# micromouse_v35.net
KiCad netlist of a schematic drawn in EAGLE
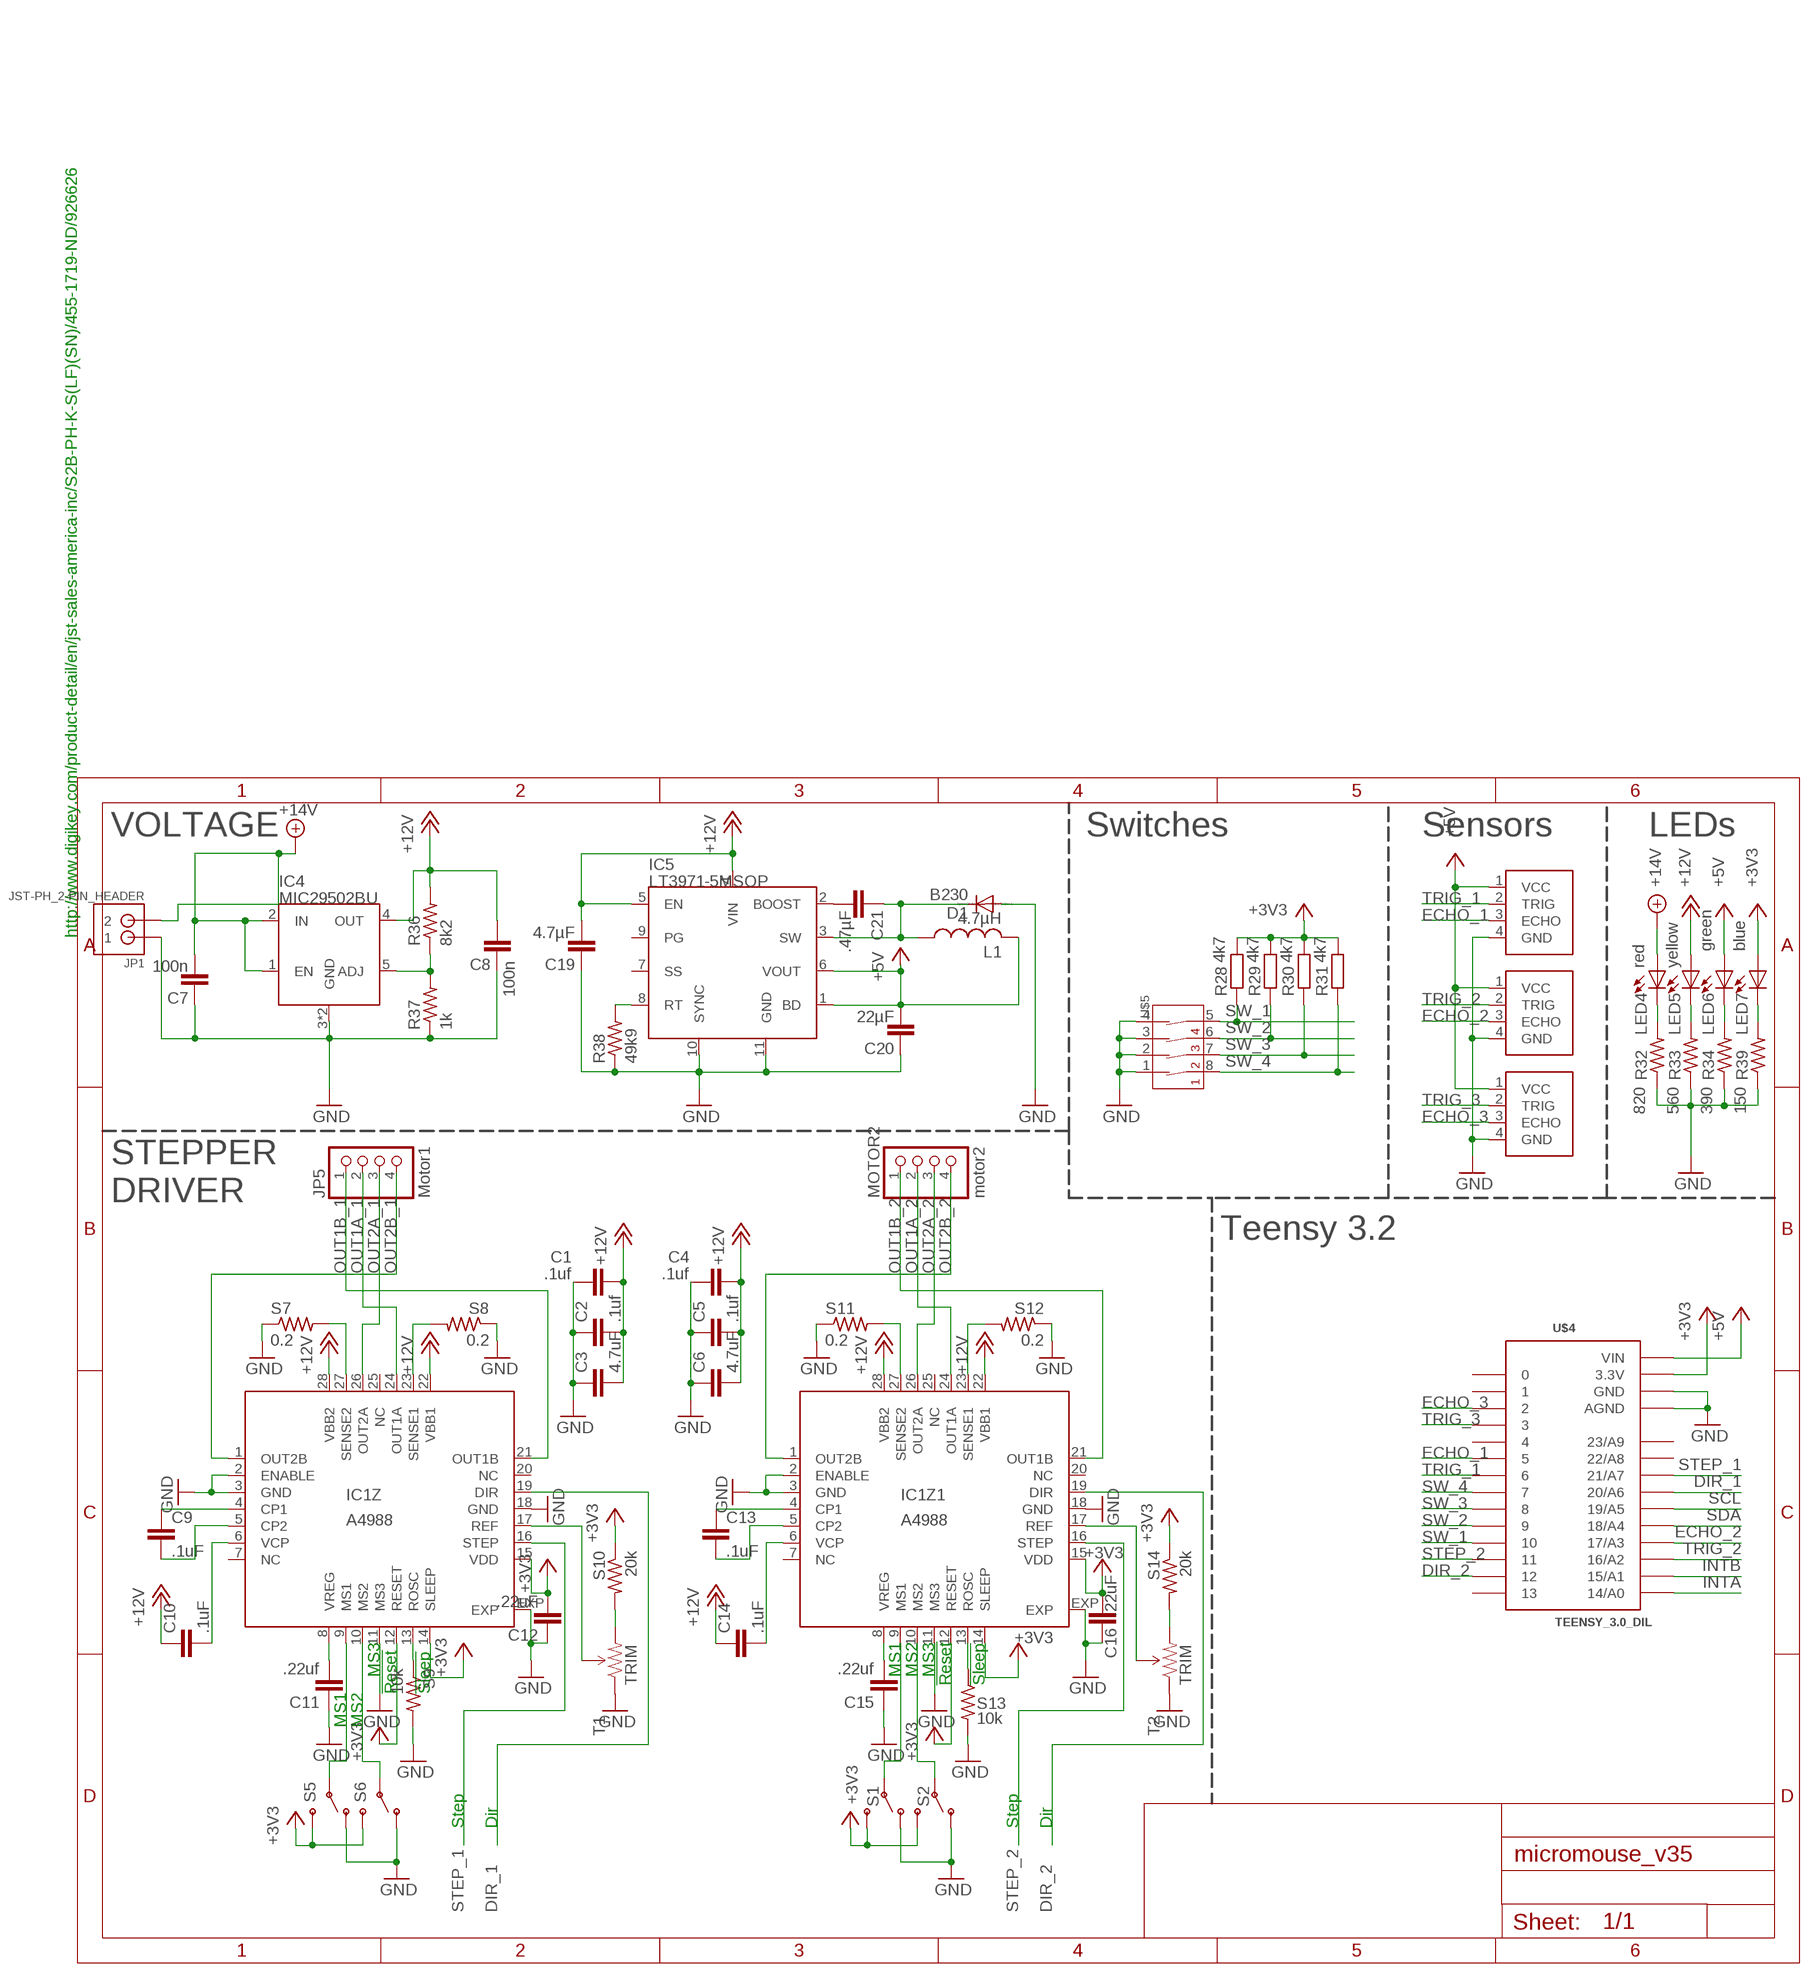
[diagram p0: schematic, sheet 1]

(export (version "E")
  (design (tool "Eeschema 10.0.6"))
  (components
    (comp (ref "C1")
      (value ".1uf")
      (footprint "eagle-import:C0603")
      (libsource (lib "eagle-import") (part "C-EUC0603"))
    )
    (comp (ref "C2")
      (value ".1uf")
      (footprint "eagle-import:C0603")
      (libsource (lib "eagle-import") (part "C-EUC0603"))
    )
    (comp (ref "C3")
      (value "4.7uF")
      (footprint "eagle-import:1206")
      (libsource (lib "eagle-import") (part "CAP1206"))
    )
    (comp (ref "C4")
      (value ".1uf")
      (footprint "eagle-import:C0603")
      (libsource (lib "eagle-import") (part "C-EUC0603"))
    )
    (comp (ref "C5")
      (value ".1uf")
      (footprint "eagle-import:C0603")
      (libsource (lib "eagle-import") (part "C-EUC0603"))
    )
    (comp (ref "C6")
      (value "4.7uF")
      (footprint "eagle-import:1206")
      (libsource (lib "eagle-import") (part "CAP1206"))
    )
    (comp (ref "C7")
      (value "100n")
      (footprint "eagle-import:C0603")
      (libsource (lib "eagle-import") (part "C-EUC0603"))
    )
    (comp (ref "C8")
      (value "100n")
      (footprint "eagle-import:C0603")
      (libsource (lib "eagle-import") (part "C-EUC0603"))
    )
    (comp (ref "C9")
      (value ".1uF")
      (footprint "eagle-import:C0603")
      (libsource (lib "eagle-import") (part "C-EUC0603"))
    )
    (comp (ref "C10")
      (value ".1uF")
      (footprint "eagle-import:C0603")
      (libsource (lib "eagle-import") (part "C-EUC0603"))
    )
    (comp (ref "C11")
      (value ".22uf")
      (footprint "eagle-import:C0603")
      (libsource (lib "eagle-import") (part "C-EUC0603"))
    )
    (comp (ref "C12")
      (value ".22uF")
      (footprint "eagle-import:C0603")
      (libsource (lib "eagle-import") (part "C-EUC0603"))
    )
    (comp (ref "C13")
      (value ".1uF")
      (footprint "eagle-import:C0603")
      (libsource (lib "eagle-import") (part "C-EUC0603"))
    )
    (comp (ref "C14")
      (value ".1uF")
      (footprint "eagle-import:C0603")
      (libsource (lib "eagle-import") (part "C-EUC0603"))
    )
    (comp (ref "C15")
      (value ".22uf")
      (footprint "eagle-import:C0603")
      (libsource (lib "eagle-import") (part "C-EUC0603"))
    )
    (comp (ref "C16")
      (value ".22uF")
      (footprint "eagle-import:C0603")
      (libsource (lib "eagle-import") (part "C-EUC0603"))
    )
    (comp (ref "C19")
      (value "4.7µF")
      (footprint "eagle-import:C0603")
      (libsource (lib "eagle-import") (part "C-EUC0603"))
    )
    (comp (ref "C20")
      (value "22µF")
      (footprint "eagle-import:C0805")
      (libsource (lib "eagle-import") (part "C-EUC0805"))
    )
    (comp (ref "C21")
      (value ".47µF")
      (footprint "eagle-import:C0603")
      (libsource (lib "eagle-import") (part "C-EUC0603"))
    )
    (comp (ref "D1")
      (value "B230")
      (footprint "eagle-import:DO-214AC")
      (libsource (lib "eagle-import") (part "DIODE-DO-214AC"))
    )
    (comp (ref "IC1Z")
      (value "A4988")
      (footprint "eagle-import:QFN28ET")
      (fields (field (name "MPN") "A4983SETTR-T"))
      (libsource (lib "eagle-import") (part "A4983"))
    )
    (comp (ref "IC1Z1")
      (value "A4988")
      (footprint "eagle-import:QFN28ET")
      (fields (field (name "MPN") "A4983SETTR-T"))
      (libsource (lib "eagle-import") (part "A4983"))
    )
    (comp (ref "IC4")
      (value "MIC29502BU")
      (footprint "eagle-import:TO-263-5")
      (libsource (lib "eagle-import") (part "MIC29502BU"))
    )
    (comp (ref "IC5")
      (value "LT3971-5MSOP")
      (footprint "eagle-import:MSOP-10")
      (libsource (lib "eagle-import") (part "LT3971-5MSOP"))
    )
    (comp (ref "JP1")
      (value "JST-PH_2-PIN_HEADER")
      (footprint "eagle-import:JST_B2B-PH_HEADER")
      (libsource (lib "eagle-import") (part "JST-PH_2-PIN_HEADER"))
    )
    (comp (ref "JP5")
      (value "Motor1")
      (footprint "eagle-import:1X04")
      (libsource (lib "eagle-import") (part "PINHD-1X4"))
    )
    (comp (ref "L1")
      (value "4.7µH")
      (footprint "eagle-import:L1812")
      (libsource (lib "eagle-import") (part "L-USL1812"))
    )
    (comp (ref "LED4")
      (value "red")
      (footprint "eagle-import:SML0603")
      (libsource (lib "eagle-import") (part "LEDSML0603"))
    )
    (comp (ref "LED5")
      (value "yellow")
      (footprint "eagle-import:SML0603")
      (libsource (lib "eagle-import") (part "LEDSML0603"))
    )
    (comp (ref "LED6")
      (value "green")
      (footprint "eagle-import:SML0603")
      (libsource (lib "eagle-import") (part "LEDSML0603"))
    )
    (comp (ref "LED7")
      (value "blue")
      (footprint "eagle-import:SML0603")
      (libsource (lib "eagle-import") (part "LEDSML0603"))
    )
    (comp (ref "MOTOR2")
      (value "motor2")
      (footprint "eagle-import:1X04")
      (libsource (lib "eagle-import") (part "PINHD-1X4"))
    )
    (comp (ref "R28")
      (value "4k7")
      (footprint "eagle-import:R0603")
      (libsource (lib "eagle-import") (part "R-EU_R0603"))
    )
    (comp (ref "R29")
      (value "4k7")
      (footprint "eagle-import:R0603")
      (libsource (lib "eagle-import") (part "R-EU_R0603"))
    )
    (comp (ref "R30")
      (value "4k7")
      (footprint "eagle-import:R0603")
      (libsource (lib "eagle-import") (part "R-EU_R0603"))
    )
    (comp (ref "R31")
      (value "4k7")
      (footprint "eagle-import:R0603")
      (libsource (lib "eagle-import") (part "R-EU_R0603"))
    )
    (comp (ref "R32")
      (value "820")
      (footprint "eagle-import:R0603")
      (libsource (lib "eagle-import") (part "R-US_R0603"))
    )
    (comp (ref "R33")
      (value "560")
      (footprint "eagle-import:R0603")
      (libsource (lib "eagle-import") (part "R-US_R0603"))
    )
    (comp (ref "R34")
      (value "390")
      (footprint "eagle-import:R0603")
      (libsource (lib "eagle-import") (part "R-US_R0603"))
    )
    (comp (ref "R36")
      (value "8k2")
      (footprint "eagle-import:R0603")
      (libsource (lib "eagle-import") (part "R-US_R0603"))
    )
    (comp (ref "R37")
      (value "1k")
      (footprint "eagle-import:R0603")
      (libsource (lib "eagle-import") (part "R-US_R0603"))
    )
    (comp (ref "R38")
      (value "49k9")
      (footprint "eagle-import:R0603")
      (libsource (lib "eagle-import") (part "R-US_R0603"))
    )
    (comp (ref "R39")
      (value "150")
      (footprint "eagle-import:R0603")
      (libsource (lib "eagle-import") (part "R-US_R0603"))
    )
    (comp (ref "S1")
      (value "SWITCH-SPDT-SMD-A")
      (footprint "eagle-import:SWITCH-SPST-SMD-A")
      (libsource (lib "eagle-import") (part "SWITCH-SPDT-SMD-A"))
    )
    (comp (ref "S2")
      (value "SWITCH-SPDT-SMD-A")
      (footprint "eagle-import:SWITCH-SPST-SMD-A")
      (libsource (lib "eagle-import") (part "SWITCH-SPDT-SMD-A"))
    )
    (comp (ref "S5")
      (value "SWITCH-SPDT-SMD-A")
      (footprint "eagle-import:SWITCH-SPST-SMD-A")
      (libsource (lib "eagle-import") (part "SWITCH-SPDT-SMD-A"))
    )
    (comp (ref "S6")
      (value "SWITCH-SPDT-SMD-A")
      (footprint "eagle-import:SWITCH-SPST-SMD-A")
      (libsource (lib "eagle-import") (part "SWITCH-SPDT-SMD-A"))
    )
    (comp (ref "S7")
      (value "0.2")
      (footprint "eagle-import:R0603")
      (libsource (lib "eagle-import") (part "R-US_R0603"))
    )
    (comp (ref "S8")
      (value "0.2")
      (footprint "eagle-import:R0603")
      (libsource (lib "eagle-import") (part "R-US_R0603"))
    )
    (comp (ref "S9")
      (value "10k")
      (footprint "eagle-import:R0603")
      (libsource (lib "eagle-import") (part "R-US_R0603"))
    )
    (comp (ref "S10")
      (value "20k")
      (footprint "eagle-import:R0603")
      (libsource (lib "eagle-import") (part "R-US_R0603"))
    )
    (comp (ref "S11")
      (value "0.2")
      (footprint "eagle-import:R0603")
      (libsource (lib "eagle-import") (part "R-US_R0603"))
    )
    (comp (ref "S12")
      (value "0.2")
      (footprint "eagle-import:R0603")
      (libsource (lib "eagle-import") (part "R-US_R0603"))
    )
    (comp (ref "S13")
      (value "10k")
      (footprint "eagle-import:R0603")
      (libsource (lib "eagle-import") (part "R-US_R0603"))
    )
    (comp (ref "S14")
      (value "20k")
      (footprint "eagle-import:R0603")
      (libsource (lib "eagle-import") (part "R-US_R0603"))
    )
    (comp (ref "SENSOR1")
      (value "HC-SR04SMD")
      (footprint "eagle-import:HC-SR04_SMD")
      (libsource (lib "eagle-import") (part "HC-SR04SMD"))
    )
    (comp (ref "SENSOR2")
      (value "HC-SR04SMD")
      (footprint "eagle-import:HC-SR04_SMD")
      (libsource (lib "eagle-import") (part "HC-SR04SMD"))
    )
    (comp (ref "SENSOR3")
      (value "HC-SR04SMD")
      (footprint "eagle-import:HC-SR04_SMD")
      (libsource (lib "eagle-import") (part "HC-SR04SMD"))
    )
    (comp (ref "T1")
      (value "TRIM")
      (footprint "eagle-import:TRIMPOT-3MM")
      (libsource (lib "eagle-import") (part "TRIMPOTSMD"))
    )
    (comp (ref "T2")
      (value "TRIM")
      (footprint "eagle-import:TRIMPOT-3MM")
      (libsource (lib "eagle-import") (part "TRIMPOTSMD"))
    )
    (comp (ref "U$4")
      (value "TEENSY_3.0_DIL")
      (footprint "eagle-import:TEENSY3-DIL")
      (libsource (lib "eagle-import") (part "TEENSY_3.0_DIL"))
    )
    (comp (ref "U$5")
      (value "4-POS-DIP")
      (footprint "eagle-import:4-POS-DIP-SMD")
      (libsource (lib "eagle-import") (part "4-POS-DIP"))
    )
  )
  (nets
    (net (code "1") (name "+3V3") (class "Default")
      (node (ref "C12") (pin "2") (pinfunction "2_2") (pintype "passive"))
      (node (ref "C16") (pin "2") (pinfunction "2_2") (pintype "passive"))
      (node (ref "IC1Z") (pin "12") (pinfunction "RESET_12") (pintype "input"))
      (node (ref "IC1Z") (pin "14") (pinfunction "SLEEP_14") (pintype "input"))
      (node (ref "IC1Z") (pin "15") (pinfunction "VDD_15") (pintype "power_in"))
      (node (ref "IC1Z1") (pin "12") (pinfunction "RESET_12") (pintype "input"))
      (node (ref "IC1Z1") (pin "14") (pinfunction "SLEEP_14") (pintype "input"))
      (node (ref "IC1Z1") (pin "15") (pinfunction "VDD_15") (pintype "power_in"))
      (node (ref "LED7") (pin "A") (pinfunction "A_A") (pintype "passive"))
      (node (ref "R28") (pin "2") (pinfunction "2_2") (pintype "passive"))
      (node (ref "R29") (pin "2") (pinfunction "2_2") (pintype "passive"))
      (node (ref "R30") (pin "2") (pinfunction "2_2") (pintype "passive"))
      (node (ref "R31") (pin "2") (pinfunction "2_2") (pintype "passive"))
      (node (ref "S1") (pin "3") (pinfunction "S_3") (pintype "passive"))
      (node (ref "S10") (pin "1") (pinfunction "1_1") (pintype "passive"))
      (node (ref "S14") (pin "1") (pinfunction "1_1") (pintype "passive"))
      (node (ref "S2") (pin "3") (pinfunction "S_3") (pintype "passive"))
      (node (ref "S5") (pin "3") (pinfunction "S_3") (pintype "passive"))
      (node (ref "S6") (pin "3") (pinfunction "S_3") (pintype "passive"))
      (node (ref "U$4") (pin "3.3V") (pinfunction "3.3V_3.3V") (pintype "power_in"))
    )
    (net (code "2") (name "+5V") (class "Default")
      (node (ref "C20") (pin "2") (pinfunction "2_2") (pintype "passive"))
      (node (ref "IC5") (pin "1") (pinfunction "BD_1") (pintype "bidirectional"))
      (node (ref "IC5") (pin "6") (pinfunction "VOUT_6") (pintype "bidirectional"))
      (node (ref "L1") (pin "2") (pinfunction "2_2") (pintype "passive"))
      (node (ref "LED6") (pin "A") (pinfunction "A_A") (pintype "passive"))
      (node (ref "SENSOR1") (pin "1") (pinfunction "VCC_1") (pintype "power_in"))
      (node (ref "SENSOR2") (pin "1") (pinfunction "VCC_1") (pintype "power_in"))
      (node (ref "SENSOR3") (pin "1") (pinfunction "VCC_1") (pintype "power_in"))
      (node (ref "U$4") (pin "VIN") (pinfunction "VIN_VIN") (pintype "power_in"))
    )
    (net (code "3") (name "+12V") (class "Default")
      (node (ref "C1") (pin "2") (pinfunction "2_2") (pintype "passive"))
      (node (ref "C10") (pin "1") (pinfunction "1_1") (pintype "passive"))
      (node (ref "C14") (pin "1") (pinfunction "1_1") (pintype "passive"))
      (node (ref "C19") (pin "2") (pinfunction "2_2") (pintype "passive"))
      (node (ref "C2") (pin "2") (pinfunction "2_2") (pintype "passive"))
      (node (ref "C3") (pin "2") (pinfunction "2_2") (pintype "passive"))
      (node (ref "C4") (pin "2") (pinfunction "2_2") (pintype "passive"))
      (node (ref "C5") (pin "2") (pinfunction "2_2") (pintype "passive"))
      (node (ref "C6") (pin "2") (pinfunction "2_2") (pintype "passive"))
      (node (ref "C8") (pin "2") (pinfunction "2_2") (pintype "passive"))
      (node (ref "IC1Z") (pin "22") (pinfunction "VBB1_22") (pintype "power_in"))
      (node (ref "IC1Z") (pin "28") (pinfunction "VBB2_28") (pintype "power_in"))
      (node (ref "IC1Z1") (pin "22") (pinfunction "VBB1_22") (pintype "power_in"))
      (node (ref "IC1Z1") (pin "28") (pinfunction "VBB2_28") (pintype "power_in"))
      (node (ref "IC4") (pin "4") (pinfunction "OUT_4") (pintype "power_in"))
      (node (ref "IC5") (pin "4") (pinfunction "VIN_4") (pintype "bidirectional"))
      (node (ref "IC5") (pin "5") (pinfunction "EN_5") (pintype "bidirectional"))
      (node (ref "LED5") (pin "A") (pinfunction "A_A") (pintype "passive"))
      (node (ref "R36") (pin "2") (pinfunction "2_2") (pintype "passive"))
    )
    (net (code "4") (name "+14V") (class "Default")
      (node (ref "C7") (pin "2") (pinfunction "2_2") (pintype "passive"))
      (node (ref "IC4") (pin "1") (pinfunction "EN_1") (pintype "input"))
      (node (ref "IC4") (pin "2") (pinfunction "IN_2") (pintype "input"))
      (node (ref "JP1") (pin "P2") (pinfunction "2_P2") (pintype "bidirectional"))
      (node (ref "LED4") (pin "A") (pinfunction "A_A") (pintype "passive"))
    )
    (net (code "5") (name "/DIR_1") (class "Default")
      (node (ref "IC1Z") (pin "19") (pinfunction "DIR_19") (pintype "input"))
      (node (ref "U$4") (pin "20/A6") (pinfunction "20/A6_20/A6") (pintype "bidirectional"))
    )
    (net (code "6") (name "/DIR_2") (class "Default")
      (node (ref "IC1Z1") (pin "19") (pinfunction "DIR_19") (pintype "input"))
      (node (ref "U$4") (pin "12") (pinfunction "12_12") (pintype "bidirectional"))
    )
    (net (code "7") (name "/ECHO_1") (class "Default")
      (node (ref "SENSOR1") (pin "3") (pinfunction "ECHO_3") (pintype "bidirectional"))
      (node (ref "U$4") (pin "5") (pinfunction "5_5") (pintype "bidirectional"))
    )
    (net (code "8") (name "/ECHO_2") (class "Default")
      (node (ref "SENSOR2") (pin "3") (pinfunction "ECHO_3") (pintype "bidirectional"))
      (node (ref "U$4") (pin "17/A3") (pinfunction "17/A3_17/A3") (pintype "bidirectional"))
    )
    (net (code "9") (name "/ECHO_3") (class "Default")
      (node (ref "SENSOR3") (pin "3") (pinfunction "ECHO_3") (pintype "bidirectional"))
      (node (ref "U$4") (pin "2") (pinfunction "2_2") (pintype "bidirectional"))
    )
    (net (code "10") (name "/INTA") (class "Default")
      (node (ref "U$4") (pin "14/A0") (pinfunction "14/A0_14/A0") (pintype "bidirectional"))
    )
    (net (code "11") (name "/INTB") (class "Default")
      (node (ref "U$4") (pin "15/A1") (pinfunction "15/A1_15/A1") (pintype "bidirectional"))
    )
    (net (code "12") (name "/OUT1A_1") (class "Default")
      (node (ref "IC1Z") (pin "24") (pinfunction "OUT1A_24") (pintype "output"))
      (node (ref "JP5") (pin "2") (pinfunction "2_2") (pintype "passive"))
    )
    (net (code "13") (name "/OUT1A_2") (class "Default")
      (node (ref "IC1Z1") (pin "24") (pinfunction "OUT1A_24") (pintype "output"))
      (node (ref "MOTOR2") (pin "2") (pinfunction "2_2") (pintype "passive"))
    )
    (net (code "14") (name "/OUT1B_1") (class "Default")
      (node (ref "IC1Z") (pin "21") (pinfunction "OUT1B_21") (pintype "output"))
      (node (ref "JP5") (pin "1") (pinfunction "1_1") (pintype "passive"))
    )
    (net (code "15") (name "/OUT1B_2") (class "Default")
      (node (ref "IC1Z1") (pin "21") (pinfunction "OUT1B_21") (pintype "output"))
      (node (ref "MOTOR2") (pin "1") (pinfunction "1_1") (pintype "passive"))
    )
    (net (code "16") (name "/OUT2A_1") (class "Default")
      (node (ref "IC1Z") (pin "26") (pinfunction "OUT2A_26") (pintype "output"))
      (node (ref "JP5") (pin "3") (pinfunction "3_3") (pintype "passive"))
    )
    (net (code "17") (name "/OUT2A_2") (class "Default")
      (node (ref "IC1Z1") (pin "26") (pinfunction "OUT2A_26") (pintype "output"))
      (node (ref "MOTOR2") (pin "3") (pinfunction "3_3") (pintype "passive"))
    )
    (net (code "18") (name "/OUT2B_1") (class "Default")
      (node (ref "IC1Z") (pin "1") (pinfunction "OUT2B_1") (pintype "output"))
      (node (ref "JP5") (pin "4") (pinfunction "4_4") (pintype "passive"))
    )
    (net (code "19") (name "/OUT2B_2") (class "Default")
      (node (ref "IC1Z1") (pin "1") (pinfunction "OUT2B_1") (pintype "output"))
      (node (ref "MOTOR2") (pin "4") (pinfunction "4_4") (pintype "passive"))
    )
    (net (code "20") (name "/SCL") (class "Default")
      (node (ref "U$4") (pin "19/A5") (pinfunction "19/A5_19/A5") (pintype "bidirectional"))
    )
    (net (code "21") (name "/SDA") (class "Default")
      (node (ref "U$4") (pin "18/A4") (pinfunction "18/A4_18/A4") (pintype "bidirectional"))
    )
    (net (code "22") (name "/STEP_1") (class "Default")
      (node (ref "IC1Z") (pin "16") (pinfunction "STEP_16") (pintype "input"))
      (node (ref "U$4") (pin "21/A7") (pinfunction "21/A7_21/A7") (pintype "bidirectional"))
    )
    (net (code "23") (name "/STEP_2") (class "Default")
      (node (ref "IC1Z1") (pin "16") (pinfunction "STEP_16") (pintype "input"))
      (node (ref "U$4") (pin "11") (pinfunction "11_11") (pintype "bidirectional"))
    )
    (net (code "24") (name "/SW_1") (class "Default")
      (node (ref "R28") (pin "1") (pinfunction "1_1") (pintype "passive"))
      (node (ref "U$4") (pin "10") (pinfunction "10_10") (pintype "bidirectional"))
      (node (ref "U$5") (pin "5") (pinfunction "4B_5") (pintype "bidirectional"))
    )
    (net (code "25") (name "/SW_2") (class "Default")
      (node (ref "R29") (pin "1") (pinfunction "1_1") (pintype "passive"))
      (node (ref "U$4") (pin "9") (pinfunction "9_9") (pintype "bidirectional"))
      (node (ref "U$5") (pin "6") (pinfunction "3B_6") (pintype "bidirectional"))
    )
    (net (code "26") (name "/SW_3") (class "Default")
      (node (ref "R30") (pin "1") (pinfunction "1_1") (pintype "passive"))
      (node (ref "U$4") (pin "8") (pinfunction "8_8") (pintype "bidirectional"))
      (node (ref "U$5") (pin "7") (pinfunction "2B_7") (pintype "bidirectional"))
    )
    (net (code "27") (name "/SW_4") (class "Default")
      (node (ref "R31") (pin "1") (pinfunction "1_1") (pintype "passive"))
      (node (ref "U$4") (pin "7") (pinfunction "7_7") (pintype "bidirectional"))
      (node (ref "U$5") (pin "8") (pinfunction "1B_8") (pintype "bidirectional"))
    )
    (net (code "28") (name "/TRIG_1") (class "Default")
      (node (ref "SENSOR1") (pin "2") (pinfunction "TRIG_2") (pintype "bidirectional"))
      (node (ref "U$4") (pin "6") (pinfunction "6_6") (pintype "bidirectional"))
    )
    (net (code "29") (name "/TRIG_2") (class "Default")
      (node (ref "SENSOR2") (pin "2") (pinfunction "TRIG_2") (pintype "bidirectional"))
      (node (ref "U$4") (pin "16/A2") (pinfunction "16/A2_16/A2") (pintype "bidirectional"))
    )
    (net (code "30") (name "/TRIG_3") (class "Default")
      (node (ref "SENSOR3") (pin "2") (pinfunction "TRIG_2") (pintype "bidirectional"))
      (node (ref "U$4") (pin "3") (pinfunction "3_3") (pintype "bidirectional"))
    )
    (net (code "31") (name "GND") (class "Default")
      (node (ref "C1") (pin "1") (pinfunction "1_1") (pintype "passive"))
      (node (ref "C11") (pin "1") (pinfunction "1_1") (pintype "passive"))
      (node (ref "C12") (pin "1") (pinfunction "1_1") (pintype "passive"))
      (node (ref "C15") (pin "1") (pinfunction "1_1") (pintype "passive"))
      (node (ref "C16") (pin "1") (pinfunction "1_1") (pintype "passive"))
      (node (ref "C19") (pin "1") (pinfunction "1_1") (pintype "passive"))
      (node (ref "C2") (pin "1") (pinfunction "1_1") (pintype "passive"))
      (node (ref "C20") (pin "1") (pinfunction "1_1") (pintype "passive"))
      (node (ref "C3") (pin "1") (pinfunction "1_1") (pintype "passive"))
      (node (ref "C4") (pin "1") (pinfunction "1_1") (pintype "passive"))
      (node (ref "C5") (pin "1") (pinfunction "1_1") (pintype "passive"))
      (node (ref "C6") (pin "1") (pinfunction "1_1") (pintype "passive"))
      (node (ref "C7") (pin "1") (pinfunction "1_1") (pintype "passive"))
      (node (ref "C8") (pin "1") (pinfunction "1_1") (pintype "passive"))
      (node (ref "D1") (pin "A") (pinfunction "A_A") (pintype "passive"))
      (node (ref "IC1Z") (pin "11") (pinfunction "MS3_11") (pintype "input"))
      (node (ref "IC1Z") (pin "18") (pinfunction "GND_18") (pintype "power_in"))
      (node (ref "IC1Z") (pin "2") (pinfunction "ENABLE_2") (pintype "input"))
      (node (ref "IC1Z") (pin "3") (pinfunction "GND_3") (pintype "power_in"))
      (node (ref "IC1Z") (pin "EXP") (pinfunction "EXP_EXP") (pintype "passive"))
      (node (ref "IC1Z1") (pin "11") (pinfunction "MS3_11") (pintype "input"))
      (node (ref "IC1Z1") (pin "18") (pinfunction "GND_18") (pintype "power_in"))
      (node (ref "IC1Z1") (pin "2") (pinfunction "ENABLE_2") (pintype "input"))
      (node (ref "IC1Z1") (pin "3") (pinfunction "GND_3") (pintype "power_in"))
      (node (ref "IC1Z1") (pin "EXP") (pinfunction "EXP_EXP") (pintype "passive"))
      (node (ref "IC4") (pin "3") (pinfunction "GND_3") (pintype "bidirectional"))
      (node (ref "IC4") (pin "6") (pinfunction "GND_6") (pintype "bidirectional"))
      (node (ref "IC5") (pin "10") (pinfunction "SYNC_10") (pintype "bidirectional"))
      (node (ref "IC5") (pin "11") (pinfunction "GND_11") (pintype "bidirectional"))
      (node (ref "JP1") (pin "P1") (pinfunction "1_P1") (pintype "bidirectional"))
      (node (ref "R32") (pin "1") (pinfunction "1_1") (pintype "passive"))
      (node (ref "R33") (pin "1") (pinfunction "1_1") (pintype "passive"))
      (node (ref "R34") (pin "1") (pinfunction "1_1") (pintype "passive"))
      (node (ref "R37") (pin "1") (pinfunction "1_1") (pintype "passive"))
      (node (ref "R38") (pin "1") (pinfunction "1_1") (pintype "passive"))
      (node (ref "R39") (pin "1") (pinfunction "1_1") (pintype "passive"))
      (node (ref "S1") (pin "1") (pinfunction "O_1") (pintype "passive"))
      (node (ref "S11") (pin "1") (pinfunction "1_1") (pintype "passive"))
      (node (ref "S12") (pin "1") (pinfunction "1_1") (pintype "passive"))
      (node (ref "S13") (pin "2") (pinfunction "2_2") (pintype "passive"))
      (node (ref "S2") (pin "1") (pinfunction "O_1") (pintype "passive"))
      (node (ref "S5") (pin "1") (pinfunction "O_1") (pintype "passive"))
      (node (ref "S6") (pin "1") (pinfunction "O_1") (pintype "passive"))
      (node (ref "S7") (pin "1") (pinfunction "1_1") (pintype "passive"))
      (node (ref "S8") (pin "1") (pinfunction "1_1") (pintype "passive"))
      (node (ref "S9") (pin "2") (pinfunction "2_2") (pintype "passive"))
      (node (ref "SENSOR1") (pin "4") (pinfunction "GND_4") (pintype "power_in"))
      (node (ref "SENSOR2") (pin "4") (pinfunction "GND_4") (pintype "power_in"))
      (node (ref "SENSOR3") (pin "4") (pinfunction "GND_4") (pintype "power_in"))
      (node (ref "T1") (pin "1") (pinfunction "CCW_1") (pintype "passive"))
      (node (ref "T2") (pin "1") (pinfunction "CCW_1") (pintype "passive"))
      (node (ref "U$4") (pin "AGND") (pinfunction "AGND_AGND") (pintype "power_in"))
      (node (ref "U$4") (pin "GND") (pinfunction "GND_GND") (pintype "power_in"))
      (node (ref "U$5") (pin "1") (pinfunction "1A_1") (pintype "bidirectional"))
      (node (ref "U$5") (pin "2") (pinfunction "2A_2") (pintype "bidirectional"))
      (node (ref "U$5") (pin "3") (pinfunction "3A_3") (pintype "bidirectional"))
      (node (ref "U$5") (pin "4") (pinfunction "4A_4") (pintype "bidirectional"))
    )
    (net (code "32") (name "Net-(IC1Z-CP1)") (class "Default")
      (node (ref "C9") (pin "1") (pinfunction "1_1") (pintype "passive"))
      (node (ref "IC1Z") (pin "4") (pinfunction "CP1_4") (pintype "passive"))
    )
    (net (code "33") (name "Net-(IC1Z-CP2)") (class "Default")
      (node (ref "C9") (pin "2") (pinfunction "2_2") (pintype "passive"))
      (node (ref "IC1Z") (pin "5") (pinfunction "CP2_5") (pintype "passive"))
    )
    (net (code "34") (name "Net-(IC1Z-MS1)") (class "Default")
      (node (ref "IC1Z") (pin "9") (pinfunction "MS1_9") (pintype "input"))
      (node (ref "S5") (pin "2") (pinfunction "P_2") (pintype "passive"))
    )
    (net (code "35") (name "Net-(IC1Z-MS2)") (class "Default")
      (node (ref "IC1Z") (pin "10") (pinfunction "MS2_10") (pintype "input"))
      (node (ref "S6") (pin "2") (pinfunction "P_2") (pintype "passive"))
    )
    (net (code "36") (name "Net-(IC1Z-REF)") (class "Default")
      (node (ref "IC1Z") (pin "17") (pinfunction "REF_17") (pintype "input"))
      (node (ref "T1") (pin "2") (pinfunction "WIPER_2") (pintype "passive"))
    )
    (net (code "37") (name "Net-(IC1Z-ROSC)") (class "Default")
      (node (ref "IC1Z") (pin "13") (pinfunction "ROSC_13") (pintype "input"))
      (node (ref "S9") (pin "1") (pinfunction "1_1") (pintype "passive"))
    )
    (net (code "38") (name "Net-(IC1Z-SENSE1)") (class "Default")
      (node (ref "IC1Z") (pin "23") (pinfunction "SENSE1_23") (pintype "input"))
      (node (ref "S8") (pin "2") (pinfunction "2_2") (pintype "passive"))
    )
    (net (code "39") (name "Net-(IC1Z-SENSE2)") (class "Default")
      (node (ref "IC1Z") (pin "27") (pinfunction "SENSE2_27") (pintype "input"))
      (node (ref "S7") (pin "2") (pinfunction "2_2") (pintype "passive"))
    )
    (net (code "40") (name "Net-(IC1Z-VCP)") (class "Default")
      (node (ref "C10") (pin "2") (pinfunction "2_2") (pintype "passive"))
      (node (ref "IC1Z") (pin "6") (pinfunction "VCP_6") (pintype "passive"))
    )
    (net (code "41") (name "Net-(IC1Z-VREG)") (class "Default")
      (node (ref "C11") (pin "2") (pinfunction "2_2") (pintype "passive"))
      (node (ref "IC1Z") (pin "8") (pinfunction "VREG_8") (pintype "passive"))
    )
    (net (code "42") (name "Net-(IC1Z1-CP1)") (class "Default")
      (node (ref "C13") (pin "1") (pinfunction "1_1") (pintype "passive"))
      (node (ref "IC1Z1") (pin "4") (pinfunction "CP1_4") (pintype "passive"))
    )
    (net (code "43") (name "Net-(IC1Z1-CP2)") (class "Default")
      (node (ref "C13") (pin "2") (pinfunction "2_2") (pintype "passive"))
      (node (ref "IC1Z1") (pin "5") (pinfunction "CP2_5") (pintype "passive"))
    )
    (net (code "44") (name "Net-(IC1Z1-MS1)") (class "Default")
      (node (ref "IC1Z1") (pin "9") (pinfunction "MS1_9") (pintype "input"))
      (node (ref "S1") (pin "2") (pinfunction "P_2") (pintype "passive"))
    )
    (net (code "45") (name "Net-(IC1Z1-MS2)") (class "Default")
      (node (ref "IC1Z1") (pin "10") (pinfunction "MS2_10") (pintype "input"))
      (node (ref "S2") (pin "2") (pinfunction "P_2") (pintype "passive"))
    )
    (net (code "46") (name "Net-(IC1Z1-REF)") (class "Default")
      (node (ref "IC1Z1") (pin "17") (pinfunction "REF_17") (pintype "input"))
      (node (ref "T2") (pin "2") (pinfunction "WIPER_2") (pintype "passive"))
    )
    (net (code "47") (name "Net-(IC1Z1-ROSC)") (class "Default")
      (node (ref "IC1Z1") (pin "13") (pinfunction "ROSC_13") (pintype "input"))
      (node (ref "S13") (pin "1") (pinfunction "1_1") (pintype "passive"))
    )
    (net (code "48") (name "Net-(IC1Z1-SENSE1)") (class "Default")
      (node (ref "IC1Z1") (pin "23") (pinfunction "SENSE1_23") (pintype "input"))
      (node (ref "S12") (pin "2") (pinfunction "2_2") (pintype "passive"))
    )
    (net (code "49") (name "Net-(IC1Z1-SENSE2)") (class "Default")
      (node (ref "IC1Z1") (pin "27") (pinfunction "SENSE2_27") (pintype "input"))
      (node (ref "S11") (pin "2") (pinfunction "2_2") (pintype "passive"))
    )
    (net (code "50") (name "Net-(IC1Z1-VCP)") (class "Default")
      (node (ref "C14") (pin "2") (pinfunction "2_2") (pintype "passive"))
      (node (ref "IC1Z1") (pin "6") (pinfunction "VCP_6") (pintype "passive"))
    )
    (net (code "51") (name "Net-(IC1Z1-VREG)") (class "Default")
      (node (ref "C15") (pin "2") (pinfunction "2_2") (pintype "passive"))
      (node (ref "IC1Z1") (pin "8") (pinfunction "VREG_8") (pintype "passive"))
    )
    (net (code "52") (name "Net-(IC4-ADJ)") (class "Default")
      (node (ref "IC4") (pin "5") (pinfunction "ADJ_5") (pintype "input"))
      (node (ref "R36") (pin "1") (pinfunction "1_1") (pintype "passive"))
      (node (ref "R37") (pin "2") (pinfunction "2_2") (pintype "passive"))
    )
    (net (code "53") (name "Net-(IC5-BOOST)") (class "Default")
      (node (ref "C21") (pin "2") (pinfunction "2_2") (pintype "passive"))
      (node (ref "IC5") (pin "2") (pinfunction "BOOST_2") (pintype "bidirectional"))
    )
    (net (code "54") (name "Net-(IC5-RT)") (class "Default")
      (node (ref "IC5") (pin "8") (pinfunction "RT_8") (pintype "bidirectional"))
      (node (ref "R38") (pin "2") (pinfunction "2_2") (pintype "passive"))
    )
    (net (code "55") (name "Net-(IC5-SW)") (class "Default")
      (node (ref "C21") (pin "1") (pinfunction "1_1") (pintype "passive"))
      (node (ref "D1") (pin "C") (pinfunction "C_C") (pintype "passive"))
      (node (ref "IC5") (pin "3") (pinfunction "SW_3") (pintype "bidirectional"))
      (node (ref "L1") (pin "1") (pinfunction "1_1") (pintype "passive"))
    )
    (net (code "56") (name "Net-(LED4-PadC)") (class "Default")
      (node (ref "LED4") (pin "C") (pinfunction "C_C") (pintype "passive"))
      (node (ref "R32") (pin "2") (pinfunction "2_2") (pintype "passive"))
    )
    (net (code "57") (name "Net-(LED5-PadC)") (class "Default")
      (node (ref "LED5") (pin "C") (pinfunction "C_C") (pintype "passive"))
      (node (ref "R33") (pin "2") (pinfunction "2_2") (pintype "passive"))
    )
    (net (code "58") (name "Net-(LED6-PadC)") (class "Default")
      (node (ref "LED6") (pin "C") (pinfunction "C_C") (pintype "passive"))
      (node (ref "R34") (pin "2") (pinfunction "2_2") (pintype "passive"))
    )
    (net (code "59") (name "Net-(LED7-PadC)") (class "Default")
      (node (ref "LED7") (pin "C") (pinfunction "C_C") (pintype "passive"))
      (node (ref "R39") (pin "2") (pinfunction "2_2") (pintype "passive"))
    )
    (net (code "60") (name "Net-(T1-CW)") (class "Default")
      (node (ref "S10") (pin "2") (pinfunction "2_2") (pintype "passive"))
      (node (ref "T1") (pin "3") (pinfunction "CW_3") (pintype "passive"))
    )
    (net (code "61") (name "Net-(T2-CW)") (class "Default")
      (node (ref "S14") (pin "2") (pinfunction "2_2") (pintype "passive"))
      (node (ref "T2") (pin "3") (pinfunction "CW_3") (pintype "passive"))
    )
    (net (code "62") (name "unconnected-(IC1Z-NC-Pad7)") (class "Default")
      (node (ref "IC1Z") (pin "7") (pinfunction "NC_7") (pintype "no_connect"))
    )
    (net (code "63") (name "unconnected-(IC1Z-NC-Pad20)") (class "Default")
      (node (ref "IC1Z") (pin "20") (pinfunction "NC_20") (pintype "no_connect"))
    )
    (net (code "64") (name "unconnected-(IC1Z-NC-Pad25)") (class "Default")
      (node (ref "IC1Z") (pin "25") (pinfunction "NC_25") (pintype "no_connect"))
    )
    (net (code "65") (name "unconnected-(IC1Z1-NC-Pad7)") (class "Default")
      (node (ref "IC1Z1") (pin "7") (pinfunction "NC_7") (pintype "no_connect"))
    )
    (net (code "66") (name "unconnected-(IC1Z1-NC-Pad20)") (class "Default")
      (node (ref "IC1Z1") (pin "20") (pinfunction "NC_20") (pintype "no_connect"))
    )
    (net (code "67") (name "unconnected-(IC1Z1-NC-Pad25)") (class "Default")
      (node (ref "IC1Z1") (pin "25") (pinfunction "NC_25") (pintype "no_connect"))
    )
    (net (code "68") (name "unconnected-(IC5-PG-Pad9)") (class "Default")
      (node (ref "IC5") (pin "9") (pinfunction "PG_9") (pintype "bidirectional"))
    )
    (net (code "69") (name "unconnected-(IC5-SS-Pad7)") (class "Default")
      (node (ref "IC5") (pin "7") (pinfunction "SS_7") (pintype "bidirectional"))
    )
    (net (code "70") (name "unconnected-(U$4-Pad0)") (class "Default")
      (node (ref "U$4") (pin "0") (pinfunction "0_0") (pintype "bidirectional"))
    )
    (net (code "71") (name "unconnected-(U$4-Pad1)") (class "Default")
      (node (ref "U$4") (pin "1") (pinfunction "1_1") (pintype "bidirectional"))
    )
    (net (code "72") (name "unconnected-(U$4-Pad4)") (class "Default")
      (node (ref "U$4") (pin "4") (pinfunction "4_4") (pintype "bidirectional"))
    )
    (net (code "73") (name "unconnected-(U$4-Pad13)") (class "Default")
      (node (ref "U$4") (pin "13") (pinfunction "13_13") (pintype "bidirectional"))
    )
    (net (code "74") (name "unconnected-(U$4-Pad22{slash}A8)") (class "Default")
      (node (ref "U$4") (pin "22/A8") (pinfunction "22/A8_22/A8") (pintype "bidirectional"))
    )
    (net (code "75") (name "unconnected-(U$4-Pad23{slash}A9)") (class "Default")
      (node (ref "U$4") (pin "23/A9") (pinfunction "23/A9_23/A9") (pintype "bidirectional"))
    )
  )
)
